# SCH_PCB-Hacker-Card_2024-02-24.net
KiCad netlist of a schematic drawn in EasyEDA
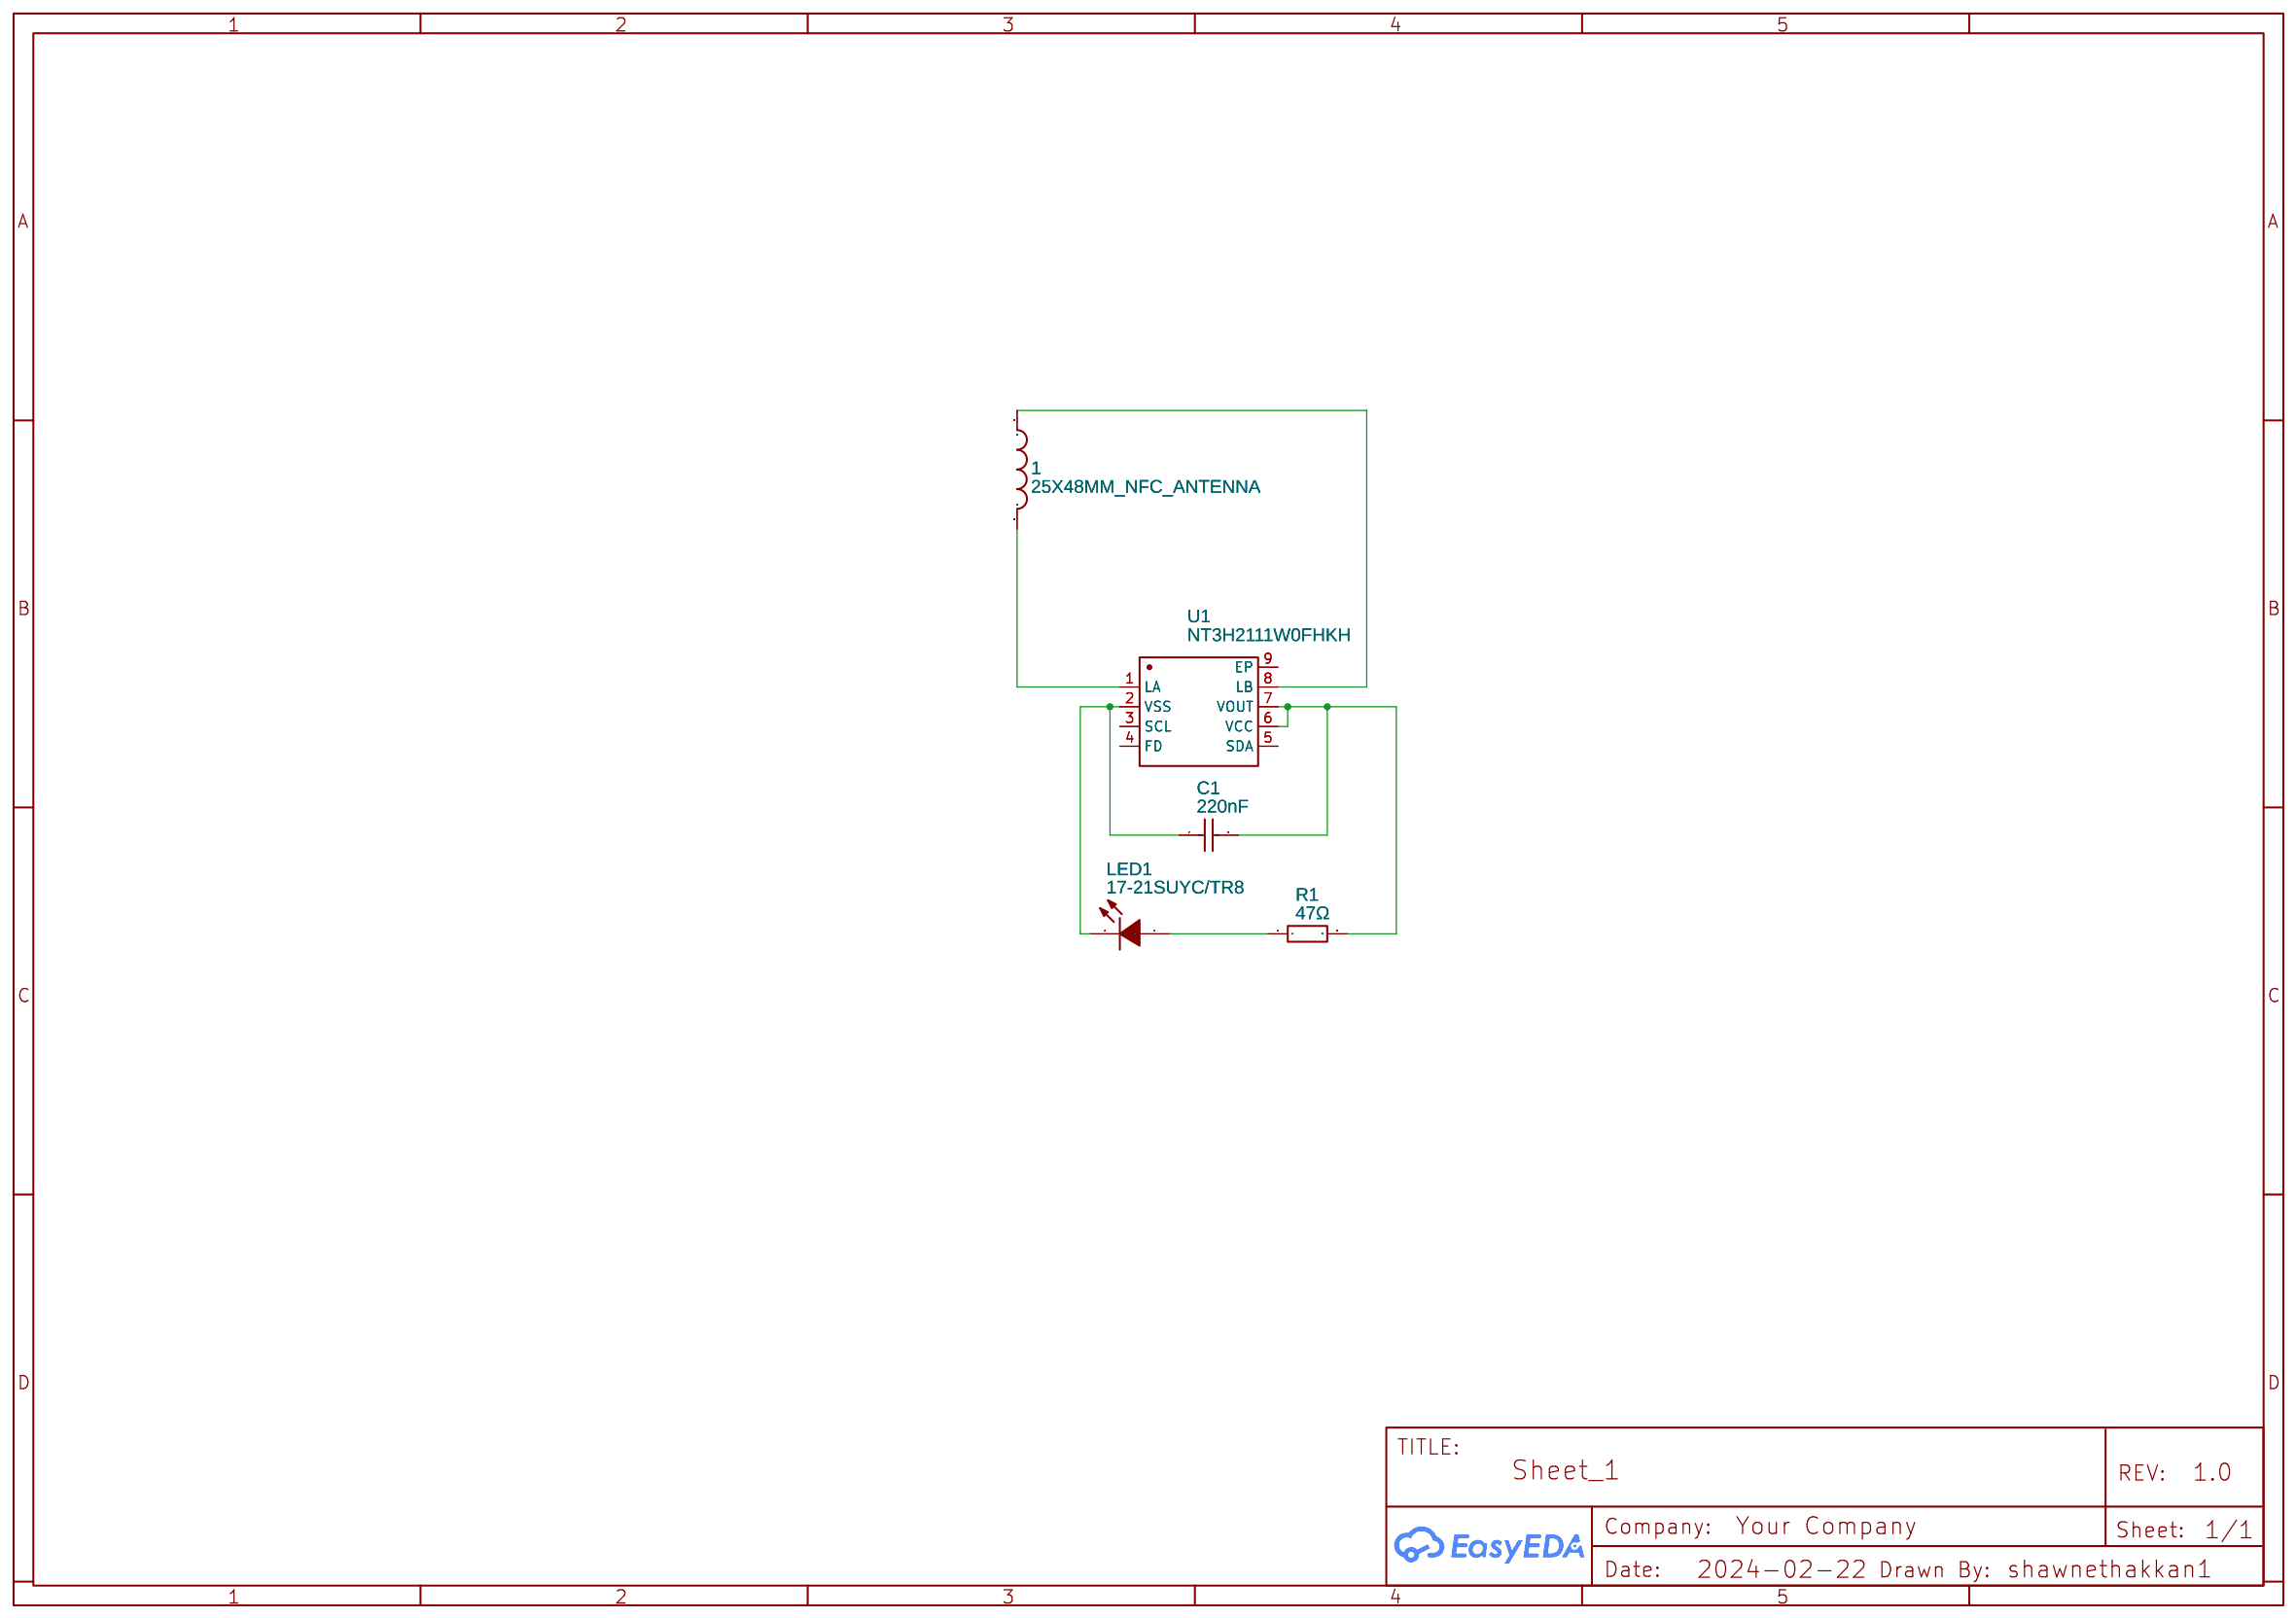
[diagram p0: schematic sheet]

(export (version "E")
  (design (tool "Eeschema 10.0.6"))
  (components
    (comp (ref "1") (value "25X48MM_NFC_ANTENNA") (libsource (lib "") (part "25X48MM_NFC_ANTENNA")))
    (comp (ref "C1")
      (value "220nF")
      (fields
        (field (name "Manufacturer Part") "CL10B224KA8NNNC")
        (field (name "Manufacturer") "SAMSUNG(三星)")
      )
      (libsource (lib "") (part "CL10B224KA8NNNC"))
    )
    (comp (ref "LED1")
      (value "17-21SUYC/TR8")
      (fields (field (name "Manufacturer Part") "KT-0805黄灯") (field (name "Manufacturer") "KENTO"))
      (libsource (lib "") (part "17-21SUYC/TR8"))
    )
    (comp (ref "R1")
      (value "47Ω")
      (fields
        (field (name "Manufacturer Part") "0603WAF470JT5E")
        (field (name "Manufacturer") "UNI-ROYAL(厚声)")
      )
      (libsource (lib "") (part "0603WAF470JT5E"))
    )
    (comp (ref "U1")
      (value "NT3H2111W0FHKH")
      (fields (field (name "Manufacturer") "NXP(恩智浦)"))
      (libsource (lib "") (part "NT3H2111W0FHKH"))
    )
  )
  (nets
    (net (code "1") (name "Net-(LED1-+)") (class "Default")
      (node (ref "LED1") (pin "1") (pinfunction "+_1") (pintype "unspecified"))
      (node (ref "R1") (pin "1") (pinfunction "1_1") (pintype "input"))
    )
    (net (code "2") (name "Net-(LED1--)") (class "Default")
      (node (ref "C1") (pin "1") (pinfunction "1_1") (pintype "input"))
      (node (ref "LED1") (pin "2") (pinfunction "-_2") (pintype "unspecified"))
      (node (ref "U1") (pin "2") (pinfunction "VSS_2") (pintype "unspecified"))
    )
    (net (code "3") (name "Net-(U1-LA)") (class "Default")
      (node (ref "1") (pin "P$2") (pinfunction "P$2_P$2") (pintype "bidirectional"))
      (node (ref "U1") (pin "1") (pinfunction "LA_1") (pintype "unspecified"))
    )
    (net (code "4") (name "Net-(U1-LB)") (class "Default")
      (node (ref "1") (pin "P$1") (pinfunction "P$1_P$1") (pintype "bidirectional"))
      (node (ref "U1") (pin "8") (pinfunction "LB_8") (pintype "unspecified"))
    )
    (net (code "5") (name "Net-(U1-VCC)") (class "Default")
      (node (ref "C1") (pin "2") (pinfunction "2_2") (pintype "input"))
      (node (ref "R1") (pin "2") (pinfunction "2_2") (pintype "input"))
      (node (ref "U1") (pin "6") (pinfunction "VCC_6") (pintype "unspecified"))
      (node (ref "U1") (pin "7") (pinfunction "VOUT_7") (pintype "unspecified"))
    )
    (net (code "6") (name "unconnected-(U1-EP-Pad9)") (class "Default")
      (node (ref "U1") (pin "9") (pinfunction "EP_9") (pintype "unspecified"))
    )
    (net (code "7") (name "unconnected-(U1-FD-Pad4)") (class "Default")
      (node (ref "U1") (pin "4") (pinfunction "FD_4") (pintype "unspecified"))
    )
    (net (code "8") (name "unconnected-(U1-SCL-Pad3)") (class "Default")
      (node (ref "U1") (pin "3") (pinfunction "SCL_3") (pintype "unspecified"))
    )
    (net (code "9") (name "unconnected-(U1-SDA-Pad5)") (class "Default")
      (node (ref "U1") (pin "5") (pinfunction "SDA_5") (pintype "unspecified"))
    )
  )
)
